# USB2Serial.net
KiCad netlist of a schematic drawn in Altium Designer
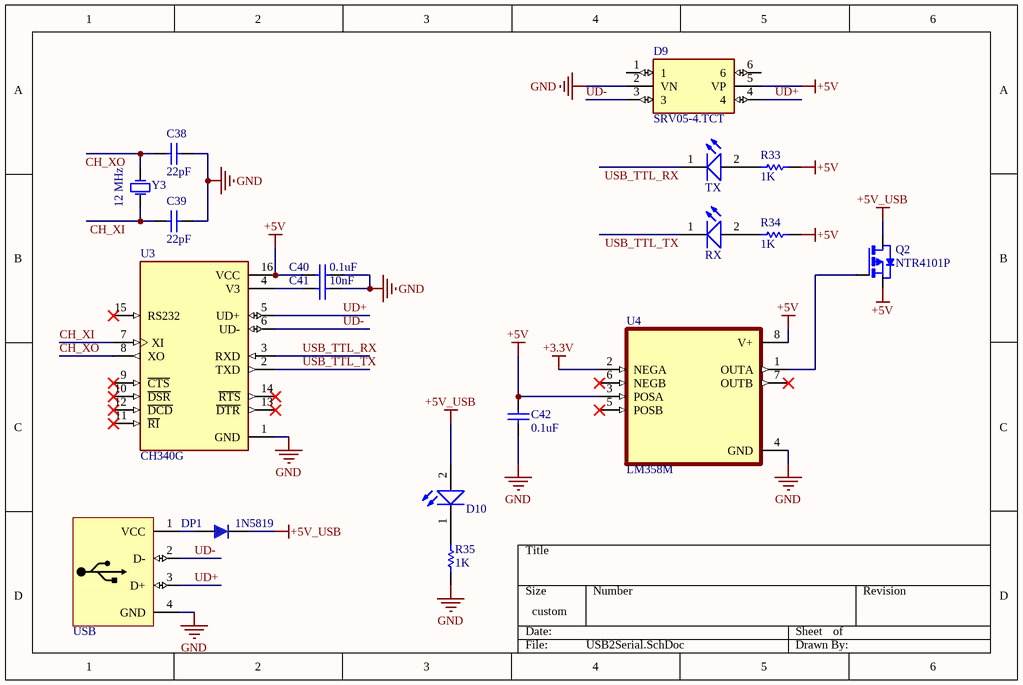
[diagram p0: USB2Serial.SchDoc]

(export (version "E")
  (design (tool "Eeschema 10.0.6"))
  (components
    (comp (ref "C38")
      (value "22pF")
      (footprint "CAPC3413X12N")
      (description "CAP 0805")
      (fields (field (name "DESIGNER") "Abbas Basereh"))
      (libsource (lib "Altium") (part "CAP SMD 0805"))
    )
    (comp (ref "C39")
      (value "22pF")
      (footprint "CAPC3413X12N")
      (description "CAP 0805")
      (fields (field (name "DESIGNER") "Abbas Basereh"))
      (libsource (lib "Altium") (part "CAP SMD 0805"))
    )
    (comp (ref "C40")
      (value "0.1uF")
      (footprint "CAPC3413X12N")
      (description "CAP 0805")
      (fields (field (name "DESIGNER") "Abbas Basereh"))
      (libsource (lib "Altium") (part "CAP SMD 0805"))
    )
    (comp (ref "C41")
      (value "10nF")
      (footprint "CAPC3413X12N")
      (description "CAP 0805")
      (fields (field (name "DESIGNER") "Abbas Basereh"))
      (libsource (lib "Altium") (part "CAP SMD 0805"))
    )
    (comp (ref "C42")
      (value "0.1uF")
      (footprint "CAPC3413X12N")
      (description "CAP 0805")
      (fields (field (name "DESIGNER") "Abbas Basereh"))
      (libsource (lib "Altium") (part "CAP SMD 0805"))
    )
    (comp (ref "D9")
      (value "SRV05-4.TCT")
      (footprint "SOT95P280X145-6N")
      (description "17.5V Clamp 12A (8/20Âµs) Ipp Tvs Diode Surface Mount SOT-23-6")
      (fields (field (name "MF") "Semtech"))
      (libsource (lib "SRV05-4.TCT") (part "SRV05-4.TCT"))
    )
    (comp (ref "D10")
      (value "LED SMD PACKAGE")
      (footprint "LED_SMD_0805")
      (description "SMD Mono-color Chip LED Waterclear")
      (fields (field (name "PART NUMBER") "150080BS75000") (field (name "PUBLISHER") "Ali Hafizi"))
      (libsource (lib "Altium") (part "LED SMD PACKAGE"))
    )
    (comp (ref "DP1")
      (value "1N5819")
      (footprint "430X270D")
      (description "Schottkey Rectifiers")
      (fields (field (name "DESIGNER") "Abbas Basereh"))
      (libsource (lib "Altium") (part "1N5819"))
    )
    (comp (ref "Q2")
      (value "NTR4101P")
      (footprint "SnapEDApcb:SOT23")
      (description "P-Channel 20V 1.8A _Ta_ 420mW _Ta_ Surface Mount SOT-23-3 _TO-236_")
      (fields (field (name "MF") "ON Semiconductor"))
      (libsource (lib "NTR4101P") (part "NTR4101P"))
    )
    (comp (ref "R33")
      (value "1K")
      (footprint "RESC3413X04N")
      (description "RES 0805")
      (fields (field (name "DESIGNER") "Abbas Basereh"))
      (libsource (lib "Altium") (part "RES 0805 0.125W"))
    )
    (comp (ref "R34")
      (value "1K")
      (footprint "RESC3413X04N")
      (description "RES 0805")
      (fields (field (name "DESIGNER") "Abbas Basereh"))
      (libsource (lib "Altium") (part "RES 0805 0.125W"))
    )
    (comp (ref "R35")
      (value "1K")
      (footprint "RESC3413X04N")
      (description "RES 0805")
      (fields (field (name "DESIGNER") "Abbas Basereh"))
      (libsource (lib "Altium") (part "RES 0805 0.125W"))
    )
    (comp (ref "RX")
      (value "LED SMD PACKAGE")
      (footprint "LED_SMD_0805")
      (description "SMD Mono-color Chip LED Waterclear")
      (fields (field (name "PART NUMBER") "150080BS75000") (field (name "PUBLISHER") "Ali Hafizi"))
      (libsource (lib "Altium") (part "LED SMD PACKAGE"))
    )
    (comp (ref "TX")
      (value "LED SMD PACKAGE")
      (footprint "LED_SMD_0805")
      (description "SMD Mono-color Chip LED Waterclear")
      (fields (field (name "PART NUMBER") "150080BS75000") (field (name "PUBLISHER") "Ali Hafizi"))
      (libsource (lib "Altium") (part "LED SMD PACKAGE"))
    )
    (comp (ref "U3")
      (value "CH340G")
      (footprint "SOIC127P600X180-16N")
      (description "USB Interface Integrated Circuit")
      (fields (field (name "MP") "Ch340G") (field (name "MF") "WCH"))
      (libsource (lib "CH340G") (part "CH340G"))
    )
    (comp (ref "U4")
      (value "LM358M")
      (footprint "SOIC127P599X175-8N")
      (description "2-Channel, 1MHz, industry standard, 32V op amp 8-SOIC 0 to 70")
      (fields (field (name "MF") "Texas Instruments"))
      (libsource (lib "LM358M") (part "LM358M"))
    )
    (comp (ref "USB")
      (value "USB Connector")
      (footprint "USB2.5-2H4E")
      (description "USB Connector-B Type")
      (libsource (lib "Altium") (part "USB B-Type"))
    )
    (comp (ref "Y3")
      (value "12 MHz")
      (footprint "Crystal SMD")
      (description "XTAL Crystal")
      (fields (field (name "DESIGNER") "ABBAS BASEREH"))
      (libsource (lib "Altium") (part "XTAL"))
    )
  )
  (nets
    (net (code "1") (name "+3.3V") (class "Default")
      (node (ref "U4") (pin "2") (pinfunction "NEGA_2") (pintype "input"))
    )
    (net (code "2") (name "+5V") (class "Default")
      (node (ref "C40") (pin "2") (pinfunction "2_2") (pintype "passive"))
      (node (ref "C42") (pin "2") (pinfunction "2_2") (pintype "passive"))
      (node (ref "D9") (pin "5") (pinfunction "VP_5") (pintype "power_in"))
      (node (ref "Q2") (pin "2") (pinfunction "S_2") (pintype "passive"))
      (node (ref "R33") (pin "1") (pinfunction "1_1") (pintype "passive"))
      (node (ref "R34") (pin "1") (pinfunction "1_1") (pintype "passive"))
      (node (ref "U3") (pin "16") (pinfunction "VCC_16") (pintype "power_in"))
      (node (ref "U4") (pin "3") (pinfunction "POSA_3") (pintype "input"))
      (node (ref "U4") (pin "8") (pinfunction "V+_8") (pintype "power_in"))
    )
    (net (code "3") (name "+5V_USB") (class "Default")
      (node (ref "D10") (pin "2") (pinfunction "A_2") (pintype "passive"))
      (node (ref "DP1") (pin "2") (pintype "passive"))
      (node (ref "Q2") (pin "3") (pinfunction "D_3") (pintype "passive"))
    )
    (net (code "4") (name "/CH_XI") (class "Default")
      (node (ref "C39") (pin "2") (pinfunction "2_2") (pintype "passive"))
      (node (ref "U3") (pin "7") (pinfunction "XI_7") (pintype "input"))
      (node (ref "Y3") (pin "1") (pinfunction "OSC1_1") (pintype "passive"))
    )
    (net (code "5") (name "/CH_XO") (class "Default")
      (node (ref "C38") (pin "2") (pinfunction "2_2") (pintype "passive"))
      (node (ref "U3") (pin "8") (pinfunction "XO_8") (pintype "output"))
      (node (ref "Y3") (pin "2") (pinfunction "OSC2_2") (pintype "passive"))
    )
    (net (code "6") (name "/UD+") (class "Default")
      (node (ref "D9") (pin "4") (pinfunction "4_4") (pintype "bidirectional"))
      (node (ref "U3") (pin "5") (pinfunction "UD+_5") (pintype "bidirectional"))
      (node (ref "USB") (pin "3") (pinfunction "D+_3") (pintype "bidirectional"))
    )
    (net (code "7") (name "/UD-") (class "Default")
      (node (ref "D9") (pin "3") (pinfunction "3_3") (pintype "bidirectional"))
      (node (ref "U3") (pin "6") (pinfunction "UD-_6") (pintype "bidirectional"))
      (node (ref "USB") (pin "2") (pinfunction "D-_2") (pintype "bidirectional"))
    )
    (net (code "8") (name "/USB_TTL_RX") (class "Default")
      (node (ref "TX") (pin "1") (pinfunction "K_1") (pintype "passive"))
      (node (ref "U3") (pin "3") (pinfunction "RXD_3") (pintype "input"))
    )
    (net (code "9") (name "/USB_TTL_TX") (class "Default")
      (node (ref "RX") (pin "1") (pinfunction "K_1") (pintype "passive"))
      (node (ref "U3") (pin "2") (pinfunction "TXD_2") (pintype "output"))
    )
    (net (code "10") (name "GND") (class "Default")
      (node (ref "C38") (pin "1") (pinfunction "1_1") (pintype "passive"))
      (node (ref "C39") (pin "1") (pinfunction "1_1") (pintype "passive"))
      (node (ref "C40") (pin "1") (pinfunction "1_1") (pintype "passive"))
      (node (ref "C41") (pin "1") (pinfunction "1_1") (pintype "passive"))
      (node (ref "C42") (pin "1") (pinfunction "1_1") (pintype "passive"))
      (node (ref "D9") (pin "2") (pinfunction "VN_2") (pintype "power_in"))
      (node (ref "R35") (pin "1") (pinfunction "1_1") (pintype "passive"))
      (node (ref "U3") (pin "1") (pinfunction "GND_1") (pintype "power_in"))
      (node (ref "U4") (pin "4") (pinfunction "GND_4") (pintype "power_in"))
      (node (ref "USB") (pin "4") (pinfunction "GND_4") (pintype "power_in"))
    )
    (net (code "11") (name "Net-(D10-K)") (class "Default")
      (node (ref "D10") (pin "1") (pinfunction "K_1") (pintype "passive"))
      (node (ref "R35") (pin "2") (pinfunction "2_2") (pintype "passive"))
    )
    (net (code "12") (name "Net-(Q2-G)") (class "Default")
      (node (ref "Q2") (pin "1") (pinfunction "G_1") (pintype "passive"))
      (node (ref "U4") (pin "1") (pinfunction "OUTA_1") (pintype "output"))
    )
    (net (code "13") (name "Net-(RX-A)") (class "Default")
      (node (ref "R34") (pin "2") (pinfunction "2_2") (pintype "passive"))
      (node (ref "RX") (pin "2") (pinfunction "A_2") (pintype "passive"))
    )
    (net (code "14") (name "Net-(TX-A)") (class "Default")
      (node (ref "R33") (pin "2") (pinfunction "2_2") (pintype "passive"))
      (node (ref "TX") (pin "2") (pinfunction "A_2") (pintype "passive"))
    )
    (net (code "15") (name "Net-(U3-V3)") (class "Default")
      (node (ref "C41") (pin "2") (pinfunction "2_2") (pintype "passive"))
      (node (ref "U3") (pin "4") (pinfunction "V3_4") (pintype "power_in"))
    )
    (net (code "16") (name "Net-(USB-VCC)") (class "Default")
      (node (ref "DP1") (pin "1") (pintype "passive"))
      (node (ref "USB") (pin "1") (pinfunction "VCC_1") (pintype "power_in"))
    )
    (net (code "17") (name "unconnected-(D9-Pad1)") (class "Default")
      (node (ref "D9") (pin "1") (pinfunction "1_1") (pintype "bidirectional"))
    )
    (net (code "18") (name "unconnected-(D9-Pad6)") (class "Default")
      (node (ref "D9") (pin "6") (pinfunction "6_6") (pintype "bidirectional"))
    )
    (net (code "19") (name "unconnected-(U3-RS232-Pad15)") (class "Default")
      (node (ref "U3") (pin "15") (pinfunction "RS232_15") (pintype "input+no_connect"))
    )
    (net (code "20") (name "unconnected-(U3-~{CTS}-Pad9)") (class "Default")
      (node (ref "U3") (pin "9") (pinfunction "~{CTS}_9") (pintype "input+no_connect"))
    )
    (net (code "21") (name "unconnected-(U3-~{DCD}-Pad12)") (class "Default")
      (node (ref "U3") (pin "12") (pinfunction "~{DCD}_12") (pintype "input+no_connect"))
    )
    (net (code "22") (name "unconnected-(U3-~{DSR}-Pad10)") (class "Default")
      (node (ref "U3") (pin "10") (pinfunction "~{DSR}_10") (pintype "input+no_connect"))
    )
    (net (code "23") (name "unconnected-(U3-~{DTR}-Pad13)") (class "Default")
      (node (ref "U3") (pin "13") (pinfunction "~{DTR}_13") (pintype "output+no_connect"))
    )
    (net (code "24") (name "unconnected-(U3-~{RI}-Pad11)") (class "Default")
      (node (ref "U3") (pin "11") (pinfunction "~{RI}_11") (pintype "input+no_connect"))
    )
    (net (code "25") (name "unconnected-(U3-~{RTS}-Pad14)") (class "Default")
      (node (ref "U3") (pin "14") (pinfunction "~{RTS}_14") (pintype "output+no_connect"))
    )
    (net (code "26") (name "unconnected-(U4-NEGB-Pad6)") (class "Default")
      (node (ref "U4") (pin "6") (pinfunction "NEGB_6") (pintype "input+no_connect"))
    )
    (net (code "27") (name "unconnected-(U4-OUTB-Pad7)") (class "Default")
      (node (ref "U4") (pin "7") (pinfunction "OUTB_7") (pintype "output+no_connect"))
    )
    (net (code "28") (name "unconnected-(U4-POSB-Pad5)") (class "Default")
      (node (ref "U4") (pin "5") (pinfunction "POSB_5") (pintype "input+no_connect"))
    )
  )
)
